# CC2538_RTC.net
KiCad netlist of a schematic drawn in Altium Designer
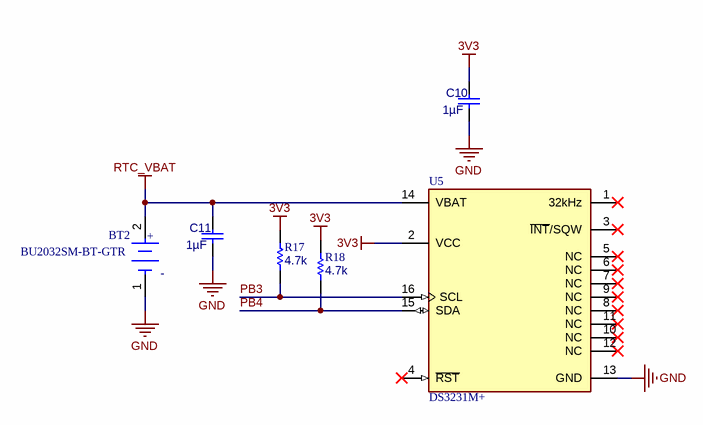
[diagram p0: [CC2538] RTC.SchDoc]

(export (version "E")
  (design (tool "Eeschema 10.0.6"))
  (components
    (comp (ref "BT2")
      (value "BU2032SM-BT-GTR")
      (footprint "FP-BU2032SM-BT-GTR-MFG")
      (description "Batteries/Accessories")
      (libsource (lib "University of Technology") (part "60d3b5b901a8747834971d0eb8cf3fd"))
    )
    (comp (ref "C10")
      (value "1µF")
      (footprint "CAP_0603")
      (description "CAP, size 0603, 1 uF, 16 VDC, 10%")
      (fields
        (field (name "MANUFACTURER PART NUMBER") "CL10B105KO8NNWC")
        (field (name "TOLERANCE") "10%")
        (field (name "SOURCE") "Capacitor_0603_10_percent.SchLib")
      )
      (libsource (lib "University of Technology") (part "010603475106.3"))
    )
    (comp (ref "C11")
      (value "1µF")
      (footprint "CAP_0603")
      (description "CAP, size 0603, 1 uF, 16 VDC, 10%")
      (fields
        (field (name "MANUFACTURER PART NUMBER") "CL10B105KO8NNWC")
        (field (name "TOLERANCE") "10%")
        (field (name "SOURCE") "Capacitor_0603_10_percent.SchLib")
      )
      (libsource (lib "University of Technology") (part "010603475106.3"))
    )
    (comp (ref "R17")
      (value "4.7k")
      (footprint "RES_0603")
      (description "RES, size 0603, 4.7 kOhm, 1/10 W, 1%")
      (fields
        (field (name "LCSC PART #") "C99782")
        (field (name "MANUFACTURER PART NUMBER") "RC0603FR-074K7L")
      )
      (libsource (lib "University of Technology") (part "00060371541"))
    )
    (comp (ref "R18")
      (value "4.7k")
      (footprint "RES_0603")
      (description "RES, size 0603, 4.7 kOhm, 1/10 W, 1%")
      (fields
        (field (name "LCSC PART #") "C99782")
        (field (name "MANUFACTURER PART NUMBER") "RC0603FR-074K7L")
      )
      (libsource (lib "University of Technology") (part "00060371541"))
    )
    (comp (ref "U5")
      (value "DS3231M+")
      (footprint "FP-W16MK-1-IPC_B")
      (description "Real Time Clock, Non-Volatile, 1 Timer(s), CMOS, PDSO16")
      (libsource (lib "University of Technology") (part "c42cf74135f9559ee4f591a2d6ab3d5"))
    )
  )
  (nets
    (net (code "1") (name "/PB3") (class "Default")
      (node (ref "R17") (pin "1") (pinfunction "1_1") (pintype "passive"))
      (node (ref "U5") (pin "16") (pinfunction "SCL_16") (pintype "input"))
    )
    (net (code "2") (name "/PB4") (class "Default")
      (node (ref "R18") (pin "1") (pinfunction "1_1") (pintype "passive"))
      (node (ref "U5") (pin "15") (pinfunction "SDA_15") (pintype "bidirectional"))
    )
    (net (code "3") (name "3V3") (class "Default")
      (node (ref "C10") (pin "2") (pinfunction "2_2") (pintype "passive"))
      (node (ref "R17") (pin "2") (pinfunction "2_2") (pintype "passive"))
      (node (ref "R18") (pin "2") (pinfunction "2_2") (pintype "passive"))
      (node (ref "U5") (pin "2") (pinfunction "VCC_2") (pintype "power_in"))
    )
    (net (code "4") (name "GND") (class "Default")
      (node (ref "BT2") (pin "1") (pinfunction "C_1") (pintype "passive"))
      (node (ref "C10") (pin "1") (pinfunction "1_1") (pintype "passive"))
      (node (ref "C11") (pin "1") (pinfunction "1_1") (pintype "passive"))
      (node (ref "U5") (pin "13") (pinfunction "GND_13") (pintype "power_in"))
    )
    (net (code "5") (name "RTC_VBAT") (class "Default")
      (node (ref "BT2") (pin "2") (pinfunction "A_2") (pintype "passive"))
      (node (ref "C11") (pin "2") (pinfunction "2_2") (pintype "passive"))
      (node (ref "U5") (pin "14") (pinfunction "VBAT_14") (pintype "power_in"))
    )
    (net (code "6") (name "unconnected-(U5-32kHz-Pad1)") (class "Default")
      (node (ref "U5") (pin "1") (pinfunction "32kHz_1") (pintype "passive+no_connect"))
    )
    (net (code "7") (name "unconnected-(U5-NC-Pad5)") (class "Default")
      (node (ref "U5") (pin "5") (pinfunction "NC_5") (pintype "passive+no_connect"))
    )
    (net (code "8") (name "unconnected-(U5-NC-Pad6)") (class "Default")
      (node (ref "U5") (pin "6") (pinfunction "NC_6") (pintype "passive+no_connect"))
    )
    (net (code "9") (name "unconnected-(U5-NC-Pad7)") (class "Default")
      (node (ref "U5") (pin "7") (pinfunction "NC_7") (pintype "passive+no_connect"))
    )
    (net (code "10") (name "unconnected-(U5-NC-Pad8)") (class "Default")
      (node (ref "U5") (pin "8") (pinfunction "NC_8") (pintype "passive+no_connect"))
    )
    (net (code "11") (name "unconnected-(U5-NC-Pad9)") (class "Default")
      (node (ref "U5") (pin "9") (pinfunction "NC_9") (pintype "passive+no_connect"))
    )
    (net (code "12") (name "unconnected-(U5-NC-Pad10)") (class "Default")
      (node (ref "U5") (pin "10") (pinfunction "NC_10") (pintype "passive+no_connect"))
    )
    (net (code "13") (name "unconnected-(U5-NC-Pad11)") (class "Default")
      (node (ref "U5") (pin "11") (pinfunction "NC_11") (pintype "passive+no_connect"))
    )
    (net (code "14") (name "unconnected-(U5-NC-Pad12)") (class "Default")
      (node (ref "U5") (pin "12") (pinfunction "NC_12") (pintype "passive+no_connect"))
    )
    (net (code "15") (name "unconnected-(U5-~{INT}{slash}SQW-Pad3)") (class "Default")
      (node (ref "U5") (pin "3") (pinfunction "~{INT}/SQW_3") (pintype "passive+no_connect"))
    )
    (net (code "16") (name "unconnected-(U5-~{RST}-Pad4)") (class "Default")
      (node (ref "U5") (pin "4") (pinfunction "~{RST}_4") (pintype "input+no_connect"))
    )
  )
)
